# STPM34_Meter.net
KiCad netlist of a schematic drawn in Altium Designer
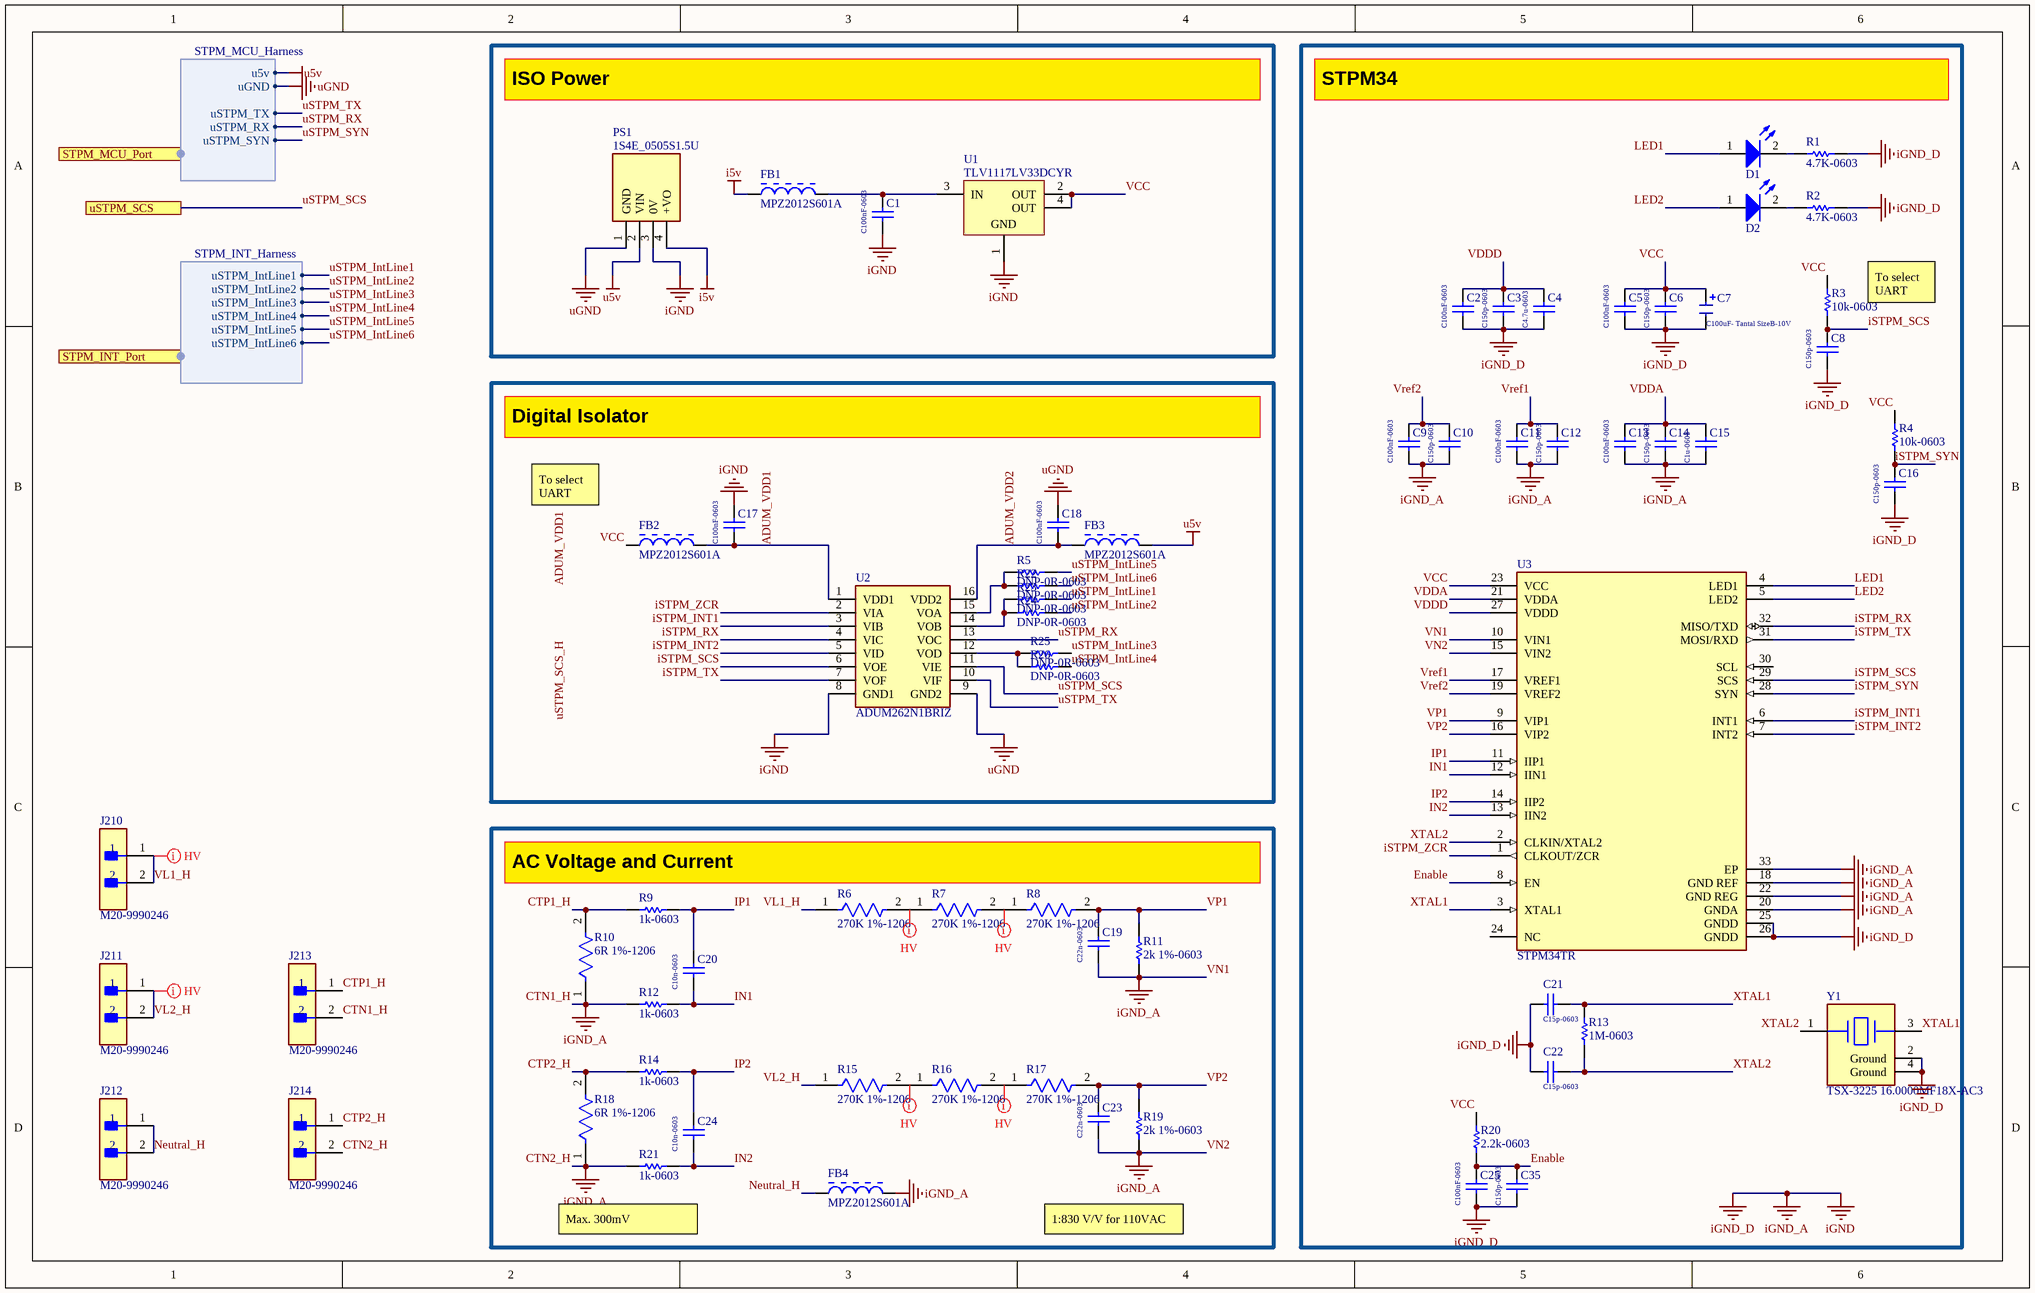
[diagram p0: STPM34_Meter.SchDoc]

(export (version "E")
  (design (tool "Eeschema 10.0.6"))
  (components
    (comp (ref "C1")
      (value "C100nF-0603")
      (footprint "CAPC1608X90X35LL10T15")
      (description "Capacitor")
      (fields (field (name "PUBLISHER") "Altium Limited"))
      (libsource (lib "Miscellaneous Devices") (part "Cap"))
    )
    (comp (ref "C2")
      (value "C100nF-0603")
      (footprint "CAPC1608X90X35LL10T15")
      (description "Capacitor")
      (fields (field (name "PUBLISHER") "Altium Limited"))
      (libsource (lib "Miscellaneous Devices") (part "Cap"))
    )
    (comp (ref "C3")
      (value "C150p-0603")
      (footprint "CAPC1608X90X35LL10T15")
      (description "Capacitor")
      (fields (field (name "PUBLISHER") "Altium Limited"))
      (libsource (lib "Miscellaneous Devices") (part "Cap"))
    )
    (comp (ref "C4")
      (value "C4.7u-0603")
      (footprint "CAPC1608X90X35LL10T15")
      (description "Capacitor")
      (fields (field (name "PUBLISHER") "Altium Limited"))
      (libsource (lib "Miscellaneous Devices") (part "Cap"))
    )
    (comp (ref "C5")
      (value "C100nF-0603")
      (footprint "CAPC1608X90X35LL10T15")
      (description "Capacitor")
      (fields (field (name "PUBLISHER") "Altium Limited"))
      (libsource (lib "Miscellaneous Devices") (part "Cap"))
    )
    (comp (ref "C6")
      (value "C150p-0603")
      (footprint "CAPC1608X90X35LL10T15")
      (description "Capacitor")
      (fields (field (name "PUBLISHER") "Altium Limited"))
      (libsource (lib "Miscellaneous Devices") (part "Cap"))
    )
    (comp (ref "C7")
      (value "C100uF- Tantal SizeB-10V")
      (footprint "Tantalium Size B")
      (libsource (lib "ZetaBoard_Lib") (part "Capacitor Tantalium"))
    )
    (comp (ref "C8")
      (value "C150p-0603")
      (footprint "CAPC1608X90X35LL10T15")
      (description "Capacitor")
      (fields (field (name "PUBLISHER") "Altium Limited"))
      (libsource (lib "Miscellaneous Devices") (part "Cap"))
    )
    (comp (ref "C9")
      (value "C100nF-0603")
      (footprint "CAPC1608X90X35LL10T15")
      (description "Capacitor")
      (fields (field (name "PUBLISHER") "Altium Limited"))
      (libsource (lib "Miscellaneous Devices") (part "Cap"))
    )
    (comp (ref "C10")
      (value "C150p-0603")
      (footprint "CAPC1608X90X35LL10T15")
      (description "Capacitor")
      (fields (field (name "PUBLISHER") "Altium Limited"))
      (libsource (lib "Miscellaneous Devices") (part "Cap"))
    )
    (comp (ref "C11")
      (value "C100nF-0603")
      (footprint "CAPC1608X90X35LL10T15")
      (description "Capacitor")
      (fields (field (name "PUBLISHER") "Altium Limited"))
      (libsource (lib "Miscellaneous Devices") (part "Cap"))
    )
    (comp (ref "C12")
      (value "C150p-0603")
      (footprint "CAPC1608X90X35LL10T15")
      (description "Capacitor")
      (fields (field (name "PUBLISHER") "Altium Limited"))
      (libsource (lib "Miscellaneous Devices") (part "Cap"))
    )
    (comp (ref "C13")
      (value "C100nF-0603")
      (footprint "CAPC1608X90X35LL10T15")
      (description "Capacitor")
      (fields (field (name "PUBLISHER") "Altium Limited"))
      (libsource (lib "Miscellaneous Devices") (part "Cap"))
    )
    (comp (ref "C14")
      (value "C150p-0603")
      (footprint "CAPC1608X90X35LL10T15")
      (description "Capacitor")
      (fields (field (name "PUBLISHER") "Altium Limited"))
      (libsource (lib "Miscellaneous Devices") (part "Cap"))
    )
    (comp (ref "C15")
      (value "C1u-0603")
      (footprint "CAPC1608X90X35LL10T15")
      (description "Capacitor")
      (fields (field (name "PUBLISHER") "Altium Limited"))
      (libsource (lib "Miscellaneous Devices") (part "Cap"))
    )
    (comp (ref "C16")
      (value "C150p-0603")
      (footprint "CAPC1608X90X35LL10T15")
      (description "Capacitor")
      (fields (field (name "PUBLISHER") "Altium Limited"))
      (libsource (lib "Miscellaneous Devices") (part "Cap"))
    )
    (comp (ref "C17")
      (value "C100nF-0603")
      (footprint "CAPC1608X90X35LL10T15")
      (description "Capacitor")
      (fields (field (name "PUBLISHER") "Altium Limited"))
      (libsource (lib "Miscellaneous Devices") (part "Cap"))
    )
    (comp (ref "C18")
      (value "C100nF-0603")
      (footprint "CAPC1608X90X35LL10T15")
      (description "Capacitor")
      (fields (field (name "PUBLISHER") "Altium Limited"))
      (libsource (lib "Miscellaneous Devices") (part "Cap"))
    )
    (comp (ref "C19")
      (value "C22n-0603")
      (footprint "CAPC1608X90X35LL10T15")
      (description "Capacitor")
      (fields (field (name "PUBLISHER") "Altium Limited"))
      (libsource (lib "Miscellaneous Devices") (part "Cap"))
    )
    (comp (ref "C20")
      (value "C10n-0603")
      (footprint "CAPC1608X90X35LL10T15")
      (description "Capacitor")
      (fields (field (name "PUBLISHER") "Altium Limited"))
      (libsource (lib "Miscellaneous Devices") (part "Cap"))
    )
    (comp (ref "C21")
      (value "C15p-0603")
      (footprint "CAPC1608X90X35LL10T15")
      (description "Capacitor")
      (fields (field (name "PUBLISHER") "Altium Limited"))
      (libsource (lib "Miscellaneous Devices") (part "Cap"))
    )
    (comp (ref "C22")
      (value "C15p-0603")
      (footprint "CAPC1608X90X35LL10T15")
      (description "Capacitor")
      (fields (field (name "PUBLISHER") "Altium Limited"))
      (libsource (lib "Miscellaneous Devices") (part "Cap"))
    )
    (comp (ref "C23")
      (value "C22n-0603")
      (footprint "CAPC1608X90X35LL10T15")
      (description "Capacitor")
      (fields (field (name "PUBLISHER") "Altium Limited"))
      (libsource (lib "Miscellaneous Devices") (part "Cap"))
    )
    (comp (ref "C24")
      (value "C10n-0603")
      (footprint "CAPC1608X90X35LL10T15")
      (description "Capacitor")
      (fields (field (name "PUBLISHER") "Altium Limited"))
      (libsource (lib "Miscellaneous Devices") (part "Cap"))
    )
    (comp (ref "C25")
      (value "C100nF-0603")
      (footprint "CAPC1608X90X35LL10T15")
      (description "Capacitor")
      (fields (field (name "PUBLISHER") "Altium Limited"))
      (libsource (lib "Miscellaneous Devices") (part "Cap"))
    )
    (comp (ref "C35")
      (value "C150p-0603")
      (footprint "CAPC1608X90X35LL10T15")
      (description "Capacitor")
      (fields (field (name "PUBLISHER") "Altium Limited"))
      (libsource (lib "Miscellaneous Devices") (part "Cap"))
    )
    (comp (ref "D1")
      (value "LED_0805_green")
      (footprint "0805-LED")
      (libsource (lib "HosseinLib") (part "LED_0805"))
    )
    (comp (ref "D2")
      (value "LED_0805_green")
      (footprint "0805-LED")
      (libsource (lib "HosseinLib") (part "LED_0805"))
    )
    (comp (ref "FB1")
      (value "MPZ2012S601A")
      (footprint "TDK-MPZ2012_V")
      (fields
        (field (name "TOLERANCE") "25%")
        (field (name "MANUFACTURER") "TDK")
        (field (name "DIGI-KEY_PART_NUMBER") "445-MPZ2012S601AT000TR-ND")
      )
      (libsource (lib "Altium Content Vault") (part "BEAD-2"))
    )
    (comp (ref "FB2")
      (value "MPZ2012S601A")
      (footprint "TDK-MPZ2012_V")
      (fields
        (field (name "TOLERANCE") "25%")
        (field (name "MANUFACTURER") "TDK")
        (field (name "DIGI-KEY_PART_NUMBER") "445-MPZ2012S601AT000TR-ND")
      )
      (libsource (lib "Altium Content Vault") (part "BEAD-2"))
    )
    (comp (ref "FB3")
      (value "MPZ2012S601A")
      (footprint "TDK-MPZ2012_V")
      (fields
        (field (name "TOLERANCE") "25%")
        (field (name "MANUFACTURER") "TDK")
        (field (name "DIGI-KEY_PART_NUMBER") "445-MPZ2012S601AT000TR-ND")
      )
      (libsource (lib "Altium Content Vault") (part "BEAD-2"))
    )
    (comp (ref "FB4")
      (value "MPZ2012S601A")
      (footprint "TDK-MPZ2012_V")
      (fields
        (field (name "TOLERANCE") "25%")
        (field (name "MANUFACTURER") "TDK")
        (field (name "DIGI-KEY_PART_NUMBER") "445-MPZ2012S601AT000TR-ND")
      )
      (libsource (lib "Altium Content Vault") (part "BEAD-2"))
    )
    (comp (ref "J210")
      (value "M20-9990246")
      (footprint "FP-M20-9990246-MFG")
      (description "CONN HEADER VERT 2POS 2.54MM")
      (fields
        (field (name "OCTOPART") "https://octopart.com/m20-9990246-harwin-2590635")
        (field (name "MANUFACTURER") "Harwin")
      )
      (libsource (lib "Altium Content Vault") (part "3bc925449376181038e59eaffc5286c"))
    )
    (comp (ref "J211")
      (value "M20-9990246")
      (footprint "FP-M20-9990246-MFG")
      (description "CONN HEADER VERT 2POS 2.54MM")
      (fields
        (field (name "OCTOPART") "https://octopart.com/m20-9990246-harwin-2590635")
        (field (name "MANUFACTURER") "Harwin")
      )
      (libsource (lib "Altium Content Vault") (part "3bc925449376181038e59eaffc5286c"))
    )
    (comp (ref "J212")
      (value "M20-9990246")
      (footprint "FP-M20-9990246-MFG")
      (description "CONN HEADER VERT 2POS 2.54MM")
      (fields
        (field (name "OCTOPART") "https://octopart.com/m20-9990246-harwin-2590635")
        (field (name "MANUFACTURER") "Harwin")
      )
      (libsource (lib "Altium Content Vault") (part "3bc925449376181038e59eaffc5286c"))
    )
    (comp (ref "J213")
      (value "M20-9990246")
      (footprint "FP-M20-9990246-MFG")
      (description "CONN HEADER VERT 2POS 2.54MM")
      (fields
        (field (name "OCTOPART") "https://octopart.com/m20-9990246-harwin-2590635")
        (field (name "MANUFACTURER") "Harwin")
      )
      (libsource (lib "Altium Content Vault") (part "3bc925449376181038e59eaffc5286c"))
    )
    (comp (ref "J214")
      (value "M20-9990246")
      (footprint "FP-M20-9990246-MFG")
      (description "CONN HEADER VERT 2POS 2.54MM")
      (fields
        (field (name "OCTOPART") "https://octopart.com/m20-9990246-harwin-2590635")
        (field (name "MANUFACTURER") "Harwin")
      )
      (libsource (lib "Altium Content Vault") (part "3bc925449376181038e59eaffc5286c"))
    )
    (comp (ref "PS1")
      (value "1S4E_0505S1.5U")
      (footprint "SamacSys:1S4E_0505S15U")
      (description "Power Supply")
      (fields (field (name "DIGI-KEY_PART_NUMBER") "3182-1S4E_0505S1.5U-ND"))
      (libsource (lib "*") (part "1S4E_0505S1.5U"))
    )
    (comp (ref "R1")
      (value "4.7K-0603")
      (footprint "FP-MCT0603-MFG")
      (description "smd")
      (fields (field (name "PUBLISHER") "Altium Limited"))
      (libsource (lib "pH_rev3") (part "ERQF06"))
    )
    (comp (ref "R2")
      (value "4.7K-0603")
      (footprint "FP-MCT0603-MFG")
      (description "smd")
      (fields (field (name "PUBLISHER") "Altium Limited"))
      (libsource (lib "pH_rev3") (part "ERQF06"))
    )
    (comp (ref "R3")
      (value "10k-0603")
      (footprint "FP-MCT0603-MFG")
      (description "Resistor")
      (fields (field (name "PUBLISHER") "Altium Limited"))
      (libsource (lib "Miscellaneous Devices") (part "Res1"))
    )
    (comp (ref "R4")
      (value "10k-0603")
      (footprint "FP-MCT0603-MFG")
      (description "Resistor")
      (fields (field (name "PUBLISHER") "Altium Limited"))
      (libsource (lib "Miscellaneous Devices") (part "Res1"))
    )
    (comp (ref "R5")
      (value "DNP-0R-0603")
      (footprint "FP-MCT0603-MFG")
      (description "Resistor")
      (fields (field (name "PUBLISHER") "Altium Limited"))
      (libsource (lib "Miscellaneous Devices") (part "Res1"))
    )
    (comp (ref "R6")
      (value "270K 1%-1206")
      (footprint "FP-CR1206-MFG")
      (description "Thick Film Chip Resistors 1206 0Ω 0.25W 5%")
      (fields (field (name "TOLERANCE") "5%") (field (name "DIGI-KEY_PART_NUMBER") "541-270KFTR-ND"))
      (libsource (lib "Altium Content Vault") (part "1029c3af85768c4190bb7ad29bc67b5"))
    )
    (comp (ref "R7")
      (value "270K 1%-1206")
      (footprint "FP-CR1206-MFG")
      (description "Thick Film Chip Resistors 1206 0Ω 0.25W 5%")
      (fields (field (name "TOLERANCE") "5%") (field (name "DIGI-KEY_PART_NUMBER") "541-270KFTR-ND"))
      (libsource (lib "Altium Content Vault") (part "1029c3af85768c4190bb7ad29bc67b5"))
    )
    (comp (ref "R8")
      (value "270K 1%-1206")
      (footprint "FP-CR1206-MFG")
      (description "Thick Film Chip Resistors 1206 0Ω 0.25W 5%")
      (fields (field (name "TOLERANCE") "5%") (field (name "DIGI-KEY_PART_NUMBER") "541-270KFTR-ND"))
      (libsource (lib "Altium Content Vault") (part "1029c3af85768c4190bb7ad29bc67b5"))
    )
    (comp (ref "R9")
      (value "1k-0603")
      (footprint "FP-MCT0603-MFG")
      (description "Resistor")
      (fields (field (name "PUBLISHER") "Altium Limited"))
      (libsource (lib "Miscellaneous Devices") (part "Res1"))
    )
    (comp (ref "R10")
      (value "6R 1%-1206")
      (footprint "FP-CR1206-MFG")
      (description "Thick Film Chip Resistors 1206 0Ω 0.25W 5%")
      (fields (field (name "TOLERANCE") "5%") (field (name "DIGI-KEY_PART_NUMBER") "541-5.90FFTR-ND"))
      (libsource (lib "Altium Content Vault") (part "1029c3af85768c4190bb7ad29bc67b5"))
    )
    (comp (ref "R11")
      (value "2k 1%-0603")
      (footprint "FP-MCT0603-MFG")
      (description "Resistor")
      (fields
        (field (name "DIGI-KEY_PART_NUMBER") "541-3953-2-ND")
        (field (name "PUBLISHER") "Altium Limited")
      )
      (libsource (lib "Miscellaneous Devices") (part "Res1"))
    )
    (comp (ref "R12")
      (value "1k-0603")
      (footprint "FP-MCT0603-MFG")
      (description "Resistor")
      (fields (field (name "PUBLISHER") "Altium Limited"))
      (libsource (lib "Miscellaneous Devices") (part "Res1"))
    )
    (comp (ref "R13")
      (value "1M-0603")
      (footprint "FP-MCT0603-MFG")
      (description "Resistor")
      (fields (field (name "PUBLISHER") "Altium Limited"))
      (libsource (lib "Miscellaneous Devices") (part "Res1"))
    )
    (comp (ref "R14")
      (value "1k-0603")
      (footprint "FP-MCT0603-MFG")
      (description "Resistor")
      (fields (field (name "PUBLISHER") "Altium Limited"))
      (libsource (lib "Miscellaneous Devices") (part "Res1"))
    )
    (comp (ref "R15")
      (value "270K 1%-1206")
      (footprint "FP-CR1206-MFG")
      (description "Thick Film Chip Resistors 1206 0Ω 0.25W 5%")
      (fields (field (name "TOLERANCE") "5%") (field (name "DIGI-KEY_PART_NUMBER") "541-270KFTR-ND"))
      (libsource (lib "Altium Content Vault") (part "1029c3af85768c4190bb7ad29bc67b5"))
    )
    (comp (ref "R16")
      (value "270K 1%-1206")
      (footprint "FP-CR1206-MFG")
      (description "Thick Film Chip Resistors 1206 0Ω 0.25W 5%")
      (fields (field (name "TOLERANCE") "5%") (field (name "DIGI-KEY_PART_NUMBER") "541-270KFTR-ND"))
      (libsource (lib "Altium Content Vault") (part "1029c3af85768c4190bb7ad29bc67b5"))
    )
    (comp (ref "R17")
      (value "270K 1%-1206")
      (footprint "FP-CR1206-MFG")
      (description "Thick Film Chip Resistors 1206 0Ω 0.25W 5%")
      (fields (field (name "TOLERANCE") "5%") (field (name "DIGI-KEY_PART_NUMBER") "541-270KFTR-ND"))
      (libsource (lib "Altium Content Vault") (part "1029c3af85768c4190bb7ad29bc67b5"))
    )
    (comp (ref "R18")
      (value "6R 1%-1206")
      (footprint "FP-CR1206-MFG")
      (description "Thick Film Chip Resistors 1206 0Ω 0.25W 5%")
      (fields (field (name "TOLERANCE") "5%") (field (name "DIGI-KEY_PART_NUMBER") "541-5.90FFTR-ND"))
      (libsource (lib "Altium Content Vault") (part "1029c3af85768c4190bb7ad29bc67b5"))
    )
    (comp (ref "R19")
      (value "2k 1%-0603")
      (footprint "FP-MCT0603-MFG")
      (description "Resistor")
      (fields
        (field (name "DIGI-KEY_PART_NUMBER") "541-3953-2-ND")
        (field (name "PUBLISHER") "Altium Limited")
      )
      (libsource (lib "Miscellaneous Devices") (part "Res1"))
    )
    (comp (ref "R20")
      (value "2.2k-0603")
      (footprint "FP-MCT0603-MFG")
      (description "Resistor")
      (fields (field (name "PUBLISHER") "Altium Limited"))
      (libsource (lib "Miscellaneous Devices") (part "Res1"))
    )
    (comp (ref "R21")
      (value "1k-0603")
      (footprint "FP-MCT0603-MFG")
      (description "Resistor")
      (fields (field (name "PUBLISHER") "Altium Limited"))
      (libsource (lib "Miscellaneous Devices") (part "Res1"))
    )
    (comp (ref "R22")
      (value "DNP-0R-0603")
      (footprint "FP-MCT0603-MFG")
      (description "Resistor")
      (fields (field (name "PUBLISHER") "Altium Limited"))
      (libsource (lib "Miscellaneous Devices") (part "Res1"))
    )
    (comp (ref "R23")
      (value "DNP-0R-0603")
      (footprint "FP-MCT0603-MFG")
      (description "Resistor")
      (fields (field (name "PUBLISHER") "Altium Limited"))
      (libsource (lib "Miscellaneous Devices") (part "Res1"))
    )
    (comp (ref "R24")
      (value "DNP-0R-0603")
      (footprint "FP-MCT0603-MFG")
      (description "Resistor")
      (fields (field (name "PUBLISHER") "Altium Limited"))
      (libsource (lib "Miscellaneous Devices") (part "Res1"))
    )
    (comp (ref "R25")
      (value "DNP-0R-0603")
      (footprint "FP-MCT0603-MFG")
      (description "Resistor")
      (fields (field (name "PUBLISHER") "Altium Limited"))
      (libsource (lib "Miscellaneous Devices") (part "Res1"))
    )
    (comp (ref "R26")
      (value "DNP-0R-0603")
      (footprint "FP-MCT0603-MFG")
      (description "Resistor")
      (fields (field (name "PUBLISHER") "Altium Limited"))
      (libsource (lib "Miscellaneous Devices") (part "Res1"))
    )
    (comp (ref "U1")
      (value "TLV1117LV33DCYR")
      (footprint "DCY0004A_N")
      (fields
        (field (name "MANUFACTURER") "Texas Instruments")
        (field (name "DIGI-KEY_PART_NUMBER") "296-28778-2-ND")
      )
      (libsource (lib "Altium Content Vault") (part "TI-TLV1117LV33DCY4"))
    )
    (comp (ref "U2")
      (value "ADUM262N1BRIZ")
      (footprint "SamacSys:SOIC127P1031X264-16N")
      (description "Integrated Circuit")
      (fields
        (field (name "MOUSER PART NUMBER") "584-ADUM262N1BRIZ")
        (field (name "DIGI-KEY_PART_NUMBER") "505-ADUM262N1WBRIZ-ND")
      )
      (libsource (lib "*") (part "ADUM262N1BRIZ"))
    )
    (comp (ref "U3")
      (value "STPM34TR")
      (footprint "FP-QFN32L-7376875-MFG")
      (description "IC ENERGY METER 1PHASE 32QFN")
      (fields (field (name "DIGI-KEY_PART_NUMBER") "497-14670-2-ND"))
      (libsource (lib "Altium Content Vault") (part "7c1c4229c747cbca8f5d05ebc9b68ec"))
    )
    (comp (ref "Y1")
      (value "TSX-3225 16.0000MF18X-AC3")
      (footprint "FP-TSX-3225-MFG")
      (description "CRYSTAL 16.0000MHZ 9PF SMD")
      (fields (field (name "TOLERANCE") "10ppm") (field (name "DIGI-KEY_PART_NUMBER") "SER3636TR-ND"))
      (libsource (lib "Altium Content Vault") (part "781bab729467ad24e026a290b9eaa03"))
    )
  )
  (nets
    (net (code "3") (name "/ADUM_VDD1") (class "Default")
      (node (ref "C17") (pin "2") (pinfunction "2_2") (pintype "passive"))
      (node (ref "FB2") (pin "2") (pinfunction "2_2") (pintype "passive"))
      (node (ref "U2") (pin "1") (pinfunction "VDD1_1") (pintype "passive"))
    )
    (net (code "4") (name "/ADUM_VDD2") (class "Default")
      (node (ref "C18") (pin "2") (pinfunction "2_2") (pintype "passive"))
      (node (ref "FB3") (pin "1") (pinfunction "1_1") (pintype "passive"))
      (node (ref "U2") (pin "16") (pinfunction "VDD2_16") (pintype "passive"))
    )
    (net (code "5") (name "/CTP1_H") (class "Default")
      (node (ref "J213") (pin "1") (pinfunction "1_1") (pintype "passive"))
      (node (ref "R10") (pin "2") (pinfunction "2_2") (pintype "passive"))
      (node (ref "R9") (pin "2") (pinfunction "2_2") (pintype "passive"))
    )
    (net (code "6") (name "/CTP2_H") (class "Default")
      (node (ref "J214") (pin "1") (pinfunction "1_1") (pintype "passive"))
      (node (ref "R14") (pin "2") (pinfunction "2_2") (pintype "passive"))
      (node (ref "R18") (pin "2") (pinfunction "2_2") (pintype "passive"))
    )
    (net (code "7") (name "/Enable") (class "Default")
      (node (ref "C25") (pin "1") (pinfunction "1_1") (pintype "passive"))
      (node (ref "C35") (pin "1") (pinfunction "1_1") (pintype "passive"))
      (node (ref "R20") (pin "1") (pinfunction "1_1") (pintype "passive"))
      (node (ref "U3") (pin "8") (pinfunction "EN_8") (pintype "input"))
    )
    (net (code "8") (name "/IN1") (class "Default")
      (node (ref "C20") (pin "2") (pinfunction "2_2") (pintype "passive"))
      (node (ref "R12") (pin "1") (pinfunction "1_1") (pintype "passive"))
      (node (ref "U3") (pin "12") (pinfunction "IIN1_12") (pintype "input"))
    )
    (net (code "9") (name "/IN2") (class "Default")
      (node (ref "C24") (pin "2") (pinfunction "2_2") (pintype "passive"))
      (node (ref "R21") (pin "1") (pinfunction "1_1") (pintype "passive"))
      (node (ref "U3") (pin "13") (pinfunction "IIN2_13") (pintype "input"))
    )
    (net (code "10") (name "/IP1") (class "Default")
      (node (ref "C20") (pin "1") (pinfunction "1_1") (pintype "passive"))
      (node (ref "R9") (pin "1") (pinfunction "1_1") (pintype "passive"))
      (node (ref "U3") (pin "11") (pinfunction "IIP1_11") (pintype "input"))
    )
    (net (code "11") (name "/IP2") (class "Default")
      (node (ref "C24") (pin "1") (pinfunction "1_1") (pintype "passive"))
      (node (ref "R14") (pin "1") (pinfunction "1_1") (pintype "passive"))
      (node (ref "U3") (pin "14") (pinfunction "IIP2_14") (pintype "input"))
    )
    (net (code "12") (name "/LED1") (class "Default")
      (node (ref "D1") (pin "1") (pinfunction "A_1") (pintype "passive"))
      (node (ref "U3") (pin "4") (pinfunction "LED1_4") (pintype "passive"))
    )
    (net (code "13") (name "/LED2") (class "Default")
      (node (ref "D2") (pin "1") (pinfunction "A_1") (pintype "passive"))
      (node (ref "U3") (pin "5") (pinfunction "LED2_5") (pintype "passive"))
    )
    (net (code "14") (name "/Neutral_H") (class "Default")
      (node (ref "FB4") (pin "1") (pinfunction "1_1") (pintype "passive"))
      (node (ref "J212") (pin "1") (pinfunction "1_1") (pintype "passive"))
      (node (ref "J212") (pin "2") (pinfunction "2_2") (pintype "passive"))
    )
    (net (code "15") (name "/VCC") (class "Default")
      (node (ref "C5") (pin "1") (pinfunction "1_1") (pintype "passive"))
      (node (ref "C6") (pin "1") (pinfunction "1_1") (pintype "passive"))
      (node (ref "C7") (pin "1") (pintype "passive"))
      (node (ref "FB2") (pin "1") (pinfunction "1_1") (pintype "passive"))
      (node (ref "R20") (pin "2") (pinfunction "2_2") (pintype "passive"))
      (node (ref "R3") (pin "2") (pinfunction "2_2") (pintype "passive"))
      (node (ref "R4") (pin "2") (pinfunction "2_2") (pintype "passive"))
      (node (ref "U1") (pin "2") (pinfunction "OUT_2") (pintype "power_in"))
      (node (ref "U1") (pin "4") (pinfunction "OUT_4") (pintype "power_in"))
      (node (ref "U3") (pin "23") (pinfunction "VCC_23") (pintype "power_in"))
    )
    (net (code "16") (name "/VDDA") (class "Default")
      (node (ref "C13") (pin "1") (pinfunction "1_1") (pintype "passive"))
      (node (ref "C14") (pin "1") (pinfunction "1_1") (pintype "passive"))
      (node (ref "C15") (pin "1") (pinfunction "1_1") (pintype "passive"))
      (node (ref "U3") (pin "21") (pinfunction "VDDA_21") (pintype "power_in"))
    )
    (net (code "17") (name "/VDDD") (class "Default")
      (node (ref "C2") (pin "1") (pinfunction "1_1") (pintype "passive"))
      (node (ref "C3") (pin "1") (pinfunction "1_1") (pintype "passive"))
      (node (ref "C4") (pin "1") (pinfunction "1_1") (pintype "passive"))
      (node (ref "U3") (pin "27") (pinfunction "VDDD_27") (pintype "power_in"))
    )
    (net (code "18") (name "/VL1_H") (class "Default")
      (node (ref "J210") (pin "1") (pinfunction "1_1") (pintype "passive"))
      (node (ref "J210") (pin "2") (pinfunction "2_2") (pintype "passive"))
      (node (ref "R6") (pin "1") (pinfunction "1_1") (pintype "passive"))
    )
    (net (code "19") (name "/VL2_H") (class "Default")
      (node (ref "J211") (pin "1") (pinfunction "1_1") (pintype "passive"))
      (node (ref "J211") (pin "2") (pinfunction "2_2") (pintype "passive"))
      (node (ref "R15") (pin "1") (pinfunction "1_1") (pintype "passive"))
    )
    (net (code "20") (name "/VP1") (class "Default")
      (node (ref "C19") (pin "1") (pinfunction "1_1") (pintype "passive"))
      (node (ref "R11") (pin "2") (pinfunction "2_2") (pintype "passive"))
      (node (ref "R8") (pin "2") (pinfunction "2_2") (pintype "passive"))
      (node (ref "U3") (pin "9") (pinfunction "VIP1_9") (pintype "power_in"))
    )
    (net (code "21") (name "/VP2") (class "Default")
      (node (ref "C23") (pin "1") (pinfunction "1_1") (pintype "passive"))
      (node (ref "R17") (pin "2") (pinfunction "2_2") (pintype "passive"))
      (node (ref "R19") (pin "2") (pinfunction "2_2") (pintype "passive"))
      (node (ref "U3") (pin "16") (pinfunction "VIP2_16") (pintype "passive"))
    )
    (net (code "22") (name "/Vref1") (class "Default")
      (node (ref "C11") (pin "1") (pinfunction "1_1") (pintype "passive"))
      (node (ref "C12") (pin "1") (pinfunction "1_1") (pintype "passive"))
      (node (ref "U3") (pin "17") (pinfunction "VREF1_17") (pintype "passive"))
    )
    (net (code "23") (name "/Vref2") (class "Default")
      (node (ref "C10") (pin "1") (pinfunction "1_1") (pintype "passive"))
      (node (ref "C9") (pin "1") (pinfunction "1_1") (pintype "passive"))
      (node (ref "U3") (pin "19") (pinfunction "VREF2_19") (pintype "passive"))
    )
    (net (code "24") (name "/XTAL1") (class "Default")
      (node (ref "C21") (pin "2") (pinfunction "2_2") (pintype "passive"))
      (node (ref "R13") (pin "2") (pinfunction "2_2") (pintype "passive"))
      (node (ref "U3") (pin "3") (pinfunction "XTAL1_3") (pintype "input"))
      (node (ref "Y1") (pin "3") (pinfunction "3_3") (pintype "passive"))
    )
    (net (code "25") (name "/XTAL2") (class "Default")
      (node (ref "C22") (pin "2") (pinfunction "2_2") (pintype "passive"))
      (node (ref "R13") (pin "1") (pinfunction "1_1") (pintype "passive"))
      (node (ref "U3") (pin "2") (pinfunction "CLKIN/XTAL2_2") (pintype "input"))
      (node (ref "Y1") (pin "1") (pinfunction "1_1") (pintype "passive"))
    )
    (net (code "26") (name "/iSTPM_INT1") (class "Default")
      (node (ref "U2") (pin "3") (pinfunction "VIB_3") (pintype "passive"))
      (node (ref "U3") (pin "6") (pinfunction "INT1_6") (pintype "input"))
    )
    (net (code "27") (name "/iSTPM_INT2") (class "Default")
      (node (ref "U2") (pin "5") (pinfunction "VID_5") (pintype "passive"))
      (node (ref "U3") (pin "7") (pinfunction "INT2_7") (pintype "input"))
    )
    (net (code "28") (name "/iSTPM_RX") (class "Default")
      (node (ref "U2") (pin "4") (pinfunction "VIC_4") (pintype "passive"))
      (node (ref "U3") (pin "32") (pinfunction "MISO/TXD_32") (pintype "bidirectional"))
    )
    (net (code "29") (name "/iSTPM_SCS") (class "Default")
      (node (ref "C8") (pin "1") (pinfunction "1_1") (pintype "passive"))
      (node (ref "R3") (pin "1") (pinfunction "1_1") (pintype "passive"))
      (node (ref "U2") (pin "6") (pinfunction "VOE_6") (pintype "passive"))
      (node (ref "U3") (pin "29") (pinfunction "SCS_29") (pintype "input"))
    )
    (net (code "30") (name "/iSTPM_SYN") (class "Default")
      (node (ref "C16") (pin "1") (pinfunction "1_1") (pintype "passive"))
      (node (ref "R4") (pin "1") (pinfunction "1_1") (pintype "passive"))
      (node (ref "U3") (pin "28") (pinfunction "SYN_28") (pintype "input"))
    )
    (net (code "31") (name "/iSTPM_TX") (class "Default")
      (node (ref "U2") (pin "7") (pinfunction "VOF_7") (pintype "passive"))
      (node (ref "U3") (pin "31") (pinfunction "MOSI/RXD_31") (pintype "output"))
    )
    (net (code "32") (name "/iSTPM_ZCR") (class "Default")
      (node (ref "U2") (pin "2") (pinfunction "VIA_2") (pintype "passive"))
      (node (ref "U3") (pin "1") (pinfunction "CLKOUT/ZCR_1") (pintype "output"))
    )
    (net (code "33") (name "/uSTPM_IntLine1") (class "Default")
      (node (ref "R23") (pin "1") (pinfunction "1_1") (pintype "passive"))
    )
    (net (code "34") (name "/uSTPM_IntLine2") (class "Default")
      (node (ref "R24") (pin "1") (pinfunction "1_1") (pintype "passive"))
    )
    (net (code "35") (name "/uSTPM_IntLine3") (class "Default")
      (node (ref "R25") (pin "1") (pinfunction "1_1") (pintype "passive"))
    )
    (net (code "36") (name "/uSTPM_IntLine4") (class "Default")
      (node (ref "R26") (pin "1") (pinfunction "1_1") (pintype "passive"))
    )
    (net (code "37") (name "/uSTPM_IntLine5") (class "Default")
      (node (ref "R5") (pin "1") (pinfunction "1_1") (pintype "passive"))
    )
    (net (code "38") (name "/uSTPM_IntLine6") (class "Default")
      (node (ref "R22") (pin "1") (pinfunction "1_1") (pintype "passive"))
    )
    (net (code "39") (name "/uSTPM_RX") (class "Default")
      (node (ref "U2") (pin "13") (pinfunction "VOC_13") (pintype "passive"))
    )
    (net (code "40") (name "/uSTPM_SCS") (class "Default")
      (node (ref "U2") (pin "11") (pinfunction "VIE_11") (pintype "passive"))
    )
    (net (code "43") (name "/uSTPM_TX") (class "Default")
      (node (ref "U2") (pin "10") (pinfunction "VIF_10") (pintype "passive"))
    )
    (net (code "46") (name "Net-(D1-K)") (class "Default")
      (node (ref "D1") (pin "2") (pinfunction "K_2") (pintype "passive"))
      (node (ref "R1") (pin "1") (pinfunction "1_1") (pintype "passive"))
    )
    (net (code "47") (name "Net-(D2-K)") (class "Default")
      (node (ref "D2") (pin "2") (pinfunction "K_2") (pintype "passive"))
      (node (ref "R2") (pin "1") (pinfunction "1_1") (pintype "passive"))
    )
    (net (code "48") (name "Net-(R6-Pad2)") (class "Default")
      (node (ref "R6") (pin "2") (pinfunction "2_2") (pintype "passive"))
      (node (ref "R7") (pin "1") (pinfunction "1_1") (pintype "passive"))
    )
    (net (code "49") (name "Net-(R7-Pad2)") (class "Default")
      (node (ref "R7") (pin "2") (pinfunction "2_2") (pintype "passive"))
      (node (ref "R8") (pin "1") (pinfunction "1_1") (pintype "passive"))
    )
    (net (code "50") (name "Net-(R15-Pad2)") (class "Default")
      (node (ref "R15") (pin "2") (pinfunction "2_2") (pintype "passive"))
      (node (ref "R16") (pin "1") (pinfunction "1_1") (pintype "passive"))
    )
    (net (code "51") (name "Net-(R16-Pad2)") (class "Default")
      (node (ref "R16") (pin "2") (pinfunction "2_2") (pintype "passive"))
      (node (ref "R17") (pin "1") (pinfunction "1_1") (pintype "passive"))
    )
    (net (code "52") (name "Net-(U1-IN)") (class "Default")
      (node (ref "C1") (pin "1") (pinfunction "1_1") (pintype "passive"))
      (node (ref "FB1") (pin "2") (pinfunction "2_2") (pintype "passive"))
      (node (ref "U1") (pin "3") (pinfunction "IN_3") (pintype "power_in"))
    )
    (net (code "53") (name "Net-(U2-VOA)") (class "Default")
      (node (ref "R22") (pin "2") (pinfunction "2_2") (pintype "passive"))
      (node (ref "R5") (pin "2") (pinfunction "2_2") (pintype "passive"))
      (node (ref "U2") (pin "15") (pinfunction "VOA_15") (pintype "passive"))
    )
    (net (code "54") (name "Net-(U2-VOB)") (class "Default")
      (node (ref "R23") (pin "2") (pinfunction "2_2") (pintype "passive"))
      (node (ref "R24") (pin "2") (pinfunction "2_2") (pintype "passive"))
      (node (ref "U2") (pin "14") (pinfunction "VOB_14") (pintype "passive"))
    )
    (net (code "55") (name "Net-(U2-VOD)") (class "Default")
      (node (ref "R25") (pin "2") (pinfunction "2_2") (pintype "passive"))
      (node (ref "R26") (pin "2") (pinfunction "2_2") (pintype "passive"))
      (node (ref "U2") (pin "12") (pinfunction "VOD_12") (pintype "passive"))
    )
    (net (code "56") (name "i5v") (class "Default")
      (node (ref "FB1") (pin "1") (pinfunction "1_1") (pintype "passive"))
      (node (ref "PS1") (pin "4") (pinfunction "+VO_4") (pintype "passive"))
    )
    (net (code "57") (name "iGND") (class "Default")
      (node (ref "C1") (pin "2") (pinfunction "2_2") (pintype "passive"))
      (node (ref "C10") (pin "2") (pinfunction "2_2") (pintype "passive"))
      (node (ref "C11") (pin "2") (pinfunction "2_2") (pintype "passive"))
      (node (ref "C12") (pin "2") (pinfunction "2_2") (pintype "passive"))
      (node (ref "C13") (pin "2") (pinfunction "2_2") (pintype "passive"))
      (node (ref "C14") (pin "2") (pinfunction "2_2") (pintype "passive"))
      (node (ref "C15") (pin "2") (pinfunction "2_2") (pintype "passive"))
      (node (ref "C16") (pin "2") (pinfunction "2_2") (pintype "passive"))
      (node (ref "C17") (pin "1") (pinfunction "1_1") (pintype "passive"))
      (node (ref "C19") (pin "2") (pinfunction "2_2") (pintype "passive"))
      (node (ref "C2") (pin "2") (pinfunction "2_2") (pintype "passive"))
      (node (ref "C21") (pin "1") (pinfunction "1_1") (pintype "passive"))
      (node (ref "C22") (pin "1") (pinfunction "1_1") (pintype "passive"))
      (node (ref "C23") (pin "2") (pinfunction "2_2") (pintype "passive"))
      (node (ref "C25") (pin "2") (pinfunction "2_2") (pintype "passive"))
      (node (ref "C3") (pin "2") (pinfunction "2_2") (pintype "passive"))
      (node (ref "C35") (pin "2") (pinfunction "2_2") (pintype "passive"))
      (node (ref "C4") (pin "2") (pinfunction "2_2") (pintype "passive"))
      (node (ref "C5") (pin "2") (pinfunction "2_2") (pintype "passive"))
      (node (ref "C6") (pin "2") (pinfunction "2_2") (pintype "passive"))
      (node (ref "C7") (pin "2") (pintype "passive"))
      (node (ref "C8") (pin "2") (pinfunction "2_2") (pintype "passive"))
      (node (ref "C9") (pin "2") (pinfunction "2_2") (pintype "passive"))
      (node (ref "FB4") (pin "2") (pinfunction "2_2") (pintype "passive"))
      (node (ref "J213") (pin "2") (pinfunction "2_2") (pintype "passive"))
      (node (ref "J214") (pin "2") (pinfunction "2_2") (pintype "passive"))
      (node (ref "PS1") (pin "3") (pinfunction "0V_3") (pintype "passive"))
      (node (ref "R1") (pin "2") (pinfunction "2_2") (pintype "passive"))
      (node (ref "R10") (pin "1") (pinfunction "1_1") (pintype "passive"))
      (node (ref "R11") (pin "1") (pinfunction "1_1") (pintype "passive"))
      (node (ref "R12") (pin "2") (pinfunction "2_2") (pintype "passive"))
      (node (ref "R18") (pin "1") (pinfunction "1_1") (pintype "passive"))
      (node (ref "R19") (pin "1") (pinfunction "1_1") (pintype "passive"))
      (node (ref "R2") (pin "2") (pinfunction "2_2") (pintype "passive"))
      (node (ref "R21") (pin "2") (pinfunction "2_2") (pintype "passive"))
      (node (ref "U1") (pin "1") (pinfunction "GND_1") (pintype "power_in"))
      (node (ref "U2") (pin "8") (pinfunction "GND1_8") (pintype "passive"))
      (node (ref "U3") (pin "10") (pinfunction "VIN1_10") (pintype "power_in"))
      (node (ref "U3") (pin "15") (pinfunction "VIN2_15") (pintype "passive"))
      (node (ref "U3") (pin "18") (pinfunction "GND_REF_18") (pintype "power_in"))
      (node (ref "U3") (pin "20") (pinfunction "GNDA_20") (pintype "power_in"))
      (node (ref "U3") (pin "22") (pinfunction "GND_REG_22") (pintype "power_in"))
      (node (ref "U3") (pin "25") (pinfunction "GNDD_25") (pintype "power_in"))
      (node (ref "U3") (pin "26") (pinfunction "GNDD_26") (pintype "power_in"))
      (node (ref "U3") (pin "33") (pinfunction "EP_33") (pintype "passive"))
      (node (ref "Y1") (pin "2") (pinfunction "Ground_2") (pintype "power_in"))
      (node (ref "Y1") (pin "4") (pinfunction "Ground_4") (pintype "power_in"))
    )
    (net (code "58") (name "u5v") (class "Default")
      (node (ref "FB3") (pin "2") (pinfunction "2_2") (pintype "passive"))
      (node (ref "PS1") (pin "2") (pinfunction "VIN_2") (pintype "passive"))
    )
    (net (code "59") (name "uGND") (class "Default")
      (node (ref "C18") (pin "1") (pinfunction "1_1") (pintype "passive"))
      (node (ref "PS1") (pin "1") (pinfunction "GND_1") (pintype "passive"))
      (node (ref "U2") (pin "9") (pinfunction "GND2_9") (pintype "passive"))
    )
    (net (code "60") (name "unconnected-(U3-NC-Pad24)") (class "Default")
      (node (ref "U3") (pin "24") (pinfunction "NC_24") (pintype "passive"))
    )
    (net (code "61") (name "unconnected-(U3-SCL-Pad30)") (class "Default")
      (node (ref "U3") (pin "30") (pinfunction "SCL_30") (pintype "input"))
    )
  )
)
